# ADC2PWM.net
KiCad netlist of a schematic drawn in EAGLE
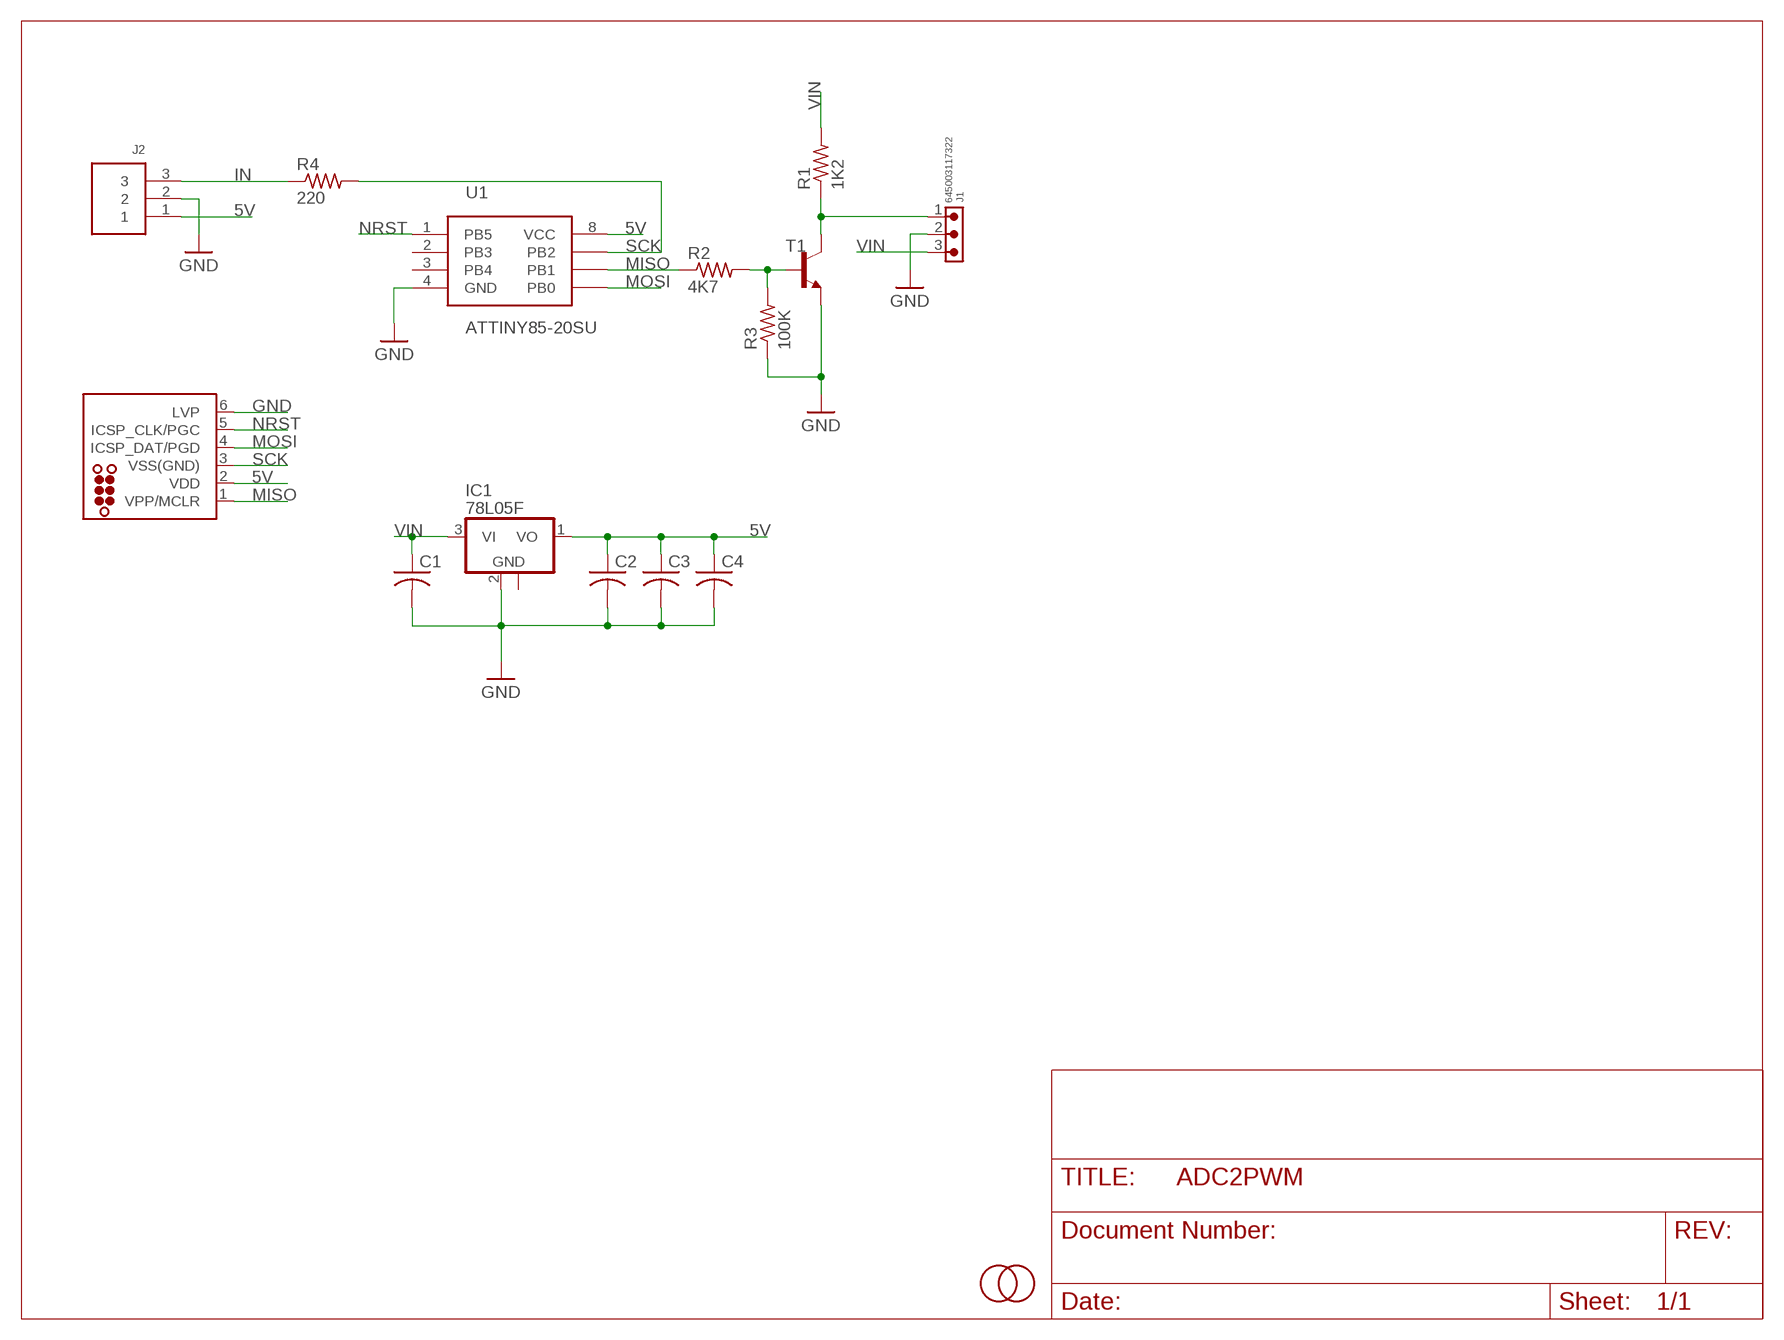
[diagram p0: schematic, sheet 1]

(export (version "E")
  (design (tool "Eeschema 10.0.6"))
  (components
    (comp (ref "C1")
      (value "C-USC0603")
      (footprint "eagle-import:C0603")
      (libsource (lib "eagle-import") (part "C-USC0603"))
    )
    (comp (ref "C2")
      (value "C-USC0603")
      (footprint "eagle-import:C0603")
      (libsource (lib "eagle-import") (part "C-USC0603"))
    )
    (comp (ref "C3")
      (value "C-USC0603")
      (footprint "eagle-import:C0603")
      (libsource (lib "eagle-import") (part "C-USC0603"))
    )
    (comp (ref "C4")
      (value "C-USC0603")
      (footprint "eagle-import:C0603")
      (libsource (lib "eagle-import") (part "C-USC0603"))
    )
    (comp (ref "IC1")
      (value "78L05F")
      (footprint "eagle-import:SOT89")
      (libsource (lib "eagle-import") (part "78LF05"))
    )
    (comp (ref "J1")
      (value "645003117322")
      (footprint "eagle-import:645003117322")
      (libsource (lib "eagle-import") (part "645003117322"))
    )
    (comp (ref "J2")
      (value "3PIN")
      (footprint "eagle-import:B3B-PH-K-S")
      (libsource (lib "eagle-import") (part "3PIN"))
    )
    (comp (ref "J3")
      (value "TC2030-MCP-NL")
      (footprint "eagle-import:TC2030-MCP-NL")
      (libsource (lib "eagle-import") (part "TC2030-MCP-NL"))
    )
    (comp (ref "R1")
      (value "1K2")
      (footprint "eagle-import:R0603")
      (libsource (lib "eagle-import") (part "R-US_R0603"))
    )
    (comp (ref "R2")
      (value "4K7")
      (footprint "eagle-import:R0603")
      (libsource (lib "eagle-import") (part "R-US_R0603"))
    )
    (comp (ref "R3")
      (value "100K")
      (footprint "eagle-import:R0603")
      (libsource (lib "eagle-import") (part "R-US_R0603"))
    )
    (comp (ref "R4")
      (value "220")
      (footprint "eagle-import:R0603")
      (libsource (lib "eagle-import") (part "R-US_R0603"))
    )
    (comp (ref "T1")
      (value "MMBT2222ALT1-NPN-SOT23-BEC")
      (footprint "eagle-import:SOT23-BEC")
      (libsource (lib "eagle-import") (part "-NPN-SOT23-BECMMBT2222ALT1"))
    )
    (comp (ref "U$1")
      (value "FIDUCIAL")
      (footprint "eagle-import:FIDUCIAL_1MM")
      (libsource (lib "eagle-import") (part "FIDUCIAL"))
    )
    (comp (ref "U$2")
      (value "FIDUCIAL")
      (footprint "eagle-import:FIDUCIAL_1MM")
      (libsource (lib "eagle-import") (part "FIDUCIAL"))
    )
    (comp (ref "U1")
      (value "ATTINY85-20SU")
      (footprint "eagle-import:SOIC-8")
      (fields
        (field (name "DIGI_KEY_PART_NUMBER") "ATTINY85-20SU-ND")
        (field (name "MANUFACTURER") "Microchip Technology")
        (field (name "CREATED_BY") "PCBLayout.com")
      )
      (libsource (lib "eagle-import") (part "ATTINY85-20SU"))
    )
  )
  (nets
    (net (code "1") (name "/5V") (class "Default")
      (node (ref "C2") (pin "1") (pinfunction "1_1") (pintype "passive"))
      (node (ref "C3") (pin "1") (pinfunction "1_1") (pintype "passive"))
      (node (ref "C4") (pin "1") (pinfunction "1_1") (pintype "passive"))
      (node (ref "IC1") (pin "1") (pinfunction "VO_1") (pintype "passive"))
      (node (ref "J2") (pin "1") (pinfunction "1_1") (pintype "bidirectional"))
      (node (ref "J3") (pin "2") (pinfunction "VDD_2") (pintype "power_in"))
      (node (ref "U1") (pin "8") (pinfunction "VCC_8") (pintype "power_in"))
    )
    (net (code "2") (name "/IN") (class "Default")
      (node (ref "J2") (pin "3") (pinfunction "3_3") (pintype "bidirectional"))
      (node (ref "R4") (pin "1") (pinfunction "1_1") (pintype "passive"))
    )
    (net (code "3") (name "/MISO") (class "Default")
      (node (ref "J3") (pin "1") (pinfunction "VPP/MCLR_1") (pintype "passive"))
      (node (ref "R2") (pin "1") (pinfunction "1_1") (pintype "passive"))
      (node (ref "U1") (pin "6") (pinfunction "PB1_6") (pintype "bidirectional"))
    )
    (net (code "4") (name "/MOSI") (class "Default")
      (node (ref "J3") (pin "4") (pinfunction "ICSP_DAT/PGD_4") (pintype "bidirectional"))
      (node (ref "U1") (pin "5") (pinfunction "PB0_5") (pintype "bidirectional"))
    )
    (net (code "5") (name "/NRST") (class "Default")
      (node (ref "J3") (pin "5") (pinfunction "ICSP_CLK/PGC_5") (pintype "output"))
      (node (ref "U1") (pin "1") (pinfunction "PB5_1") (pintype "bidirectional"))
    )
    (net (code "6") (name "/SCK") (class "Default")
      (node (ref "J3") (pin "3") (pinfunction "VSS(GND)_3") (pintype "power_in"))
      (node (ref "R4") (pin "2") (pinfunction "2_2") (pintype "passive"))
      (node (ref "U1") (pin "7") (pinfunction "PB2_7") (pintype "bidirectional"))
    )
    (net (code "7") (name "/VIN") (class "Default")
      (node (ref "C1") (pin "1") (pinfunction "1_1") (pintype "passive"))
      (node (ref "IC1") (pin "3") (pinfunction "VI_3") (pintype "input"))
      (node (ref "J1") (pin "3") (pinfunction "3_3") (pintype "passive"))
      (node (ref "R1") (pin "2") (pinfunction "2_2") (pintype "passive"))
    )
    (net (code "8") (name "GND") (class "Default")
      (node (ref "C1") (pin "2") (pinfunction "2_2") (pintype "passive"))
      (node (ref "C2") (pin "2") (pinfunction "2_2") (pintype "passive"))
      (node (ref "C3") (pin "2") (pinfunction "2_2") (pintype "passive"))
      (node (ref "C4") (pin "2") (pinfunction "2_2") (pintype "passive"))
      (node (ref "IC1") (pin "2") (pinfunction "GND_2") (pintype "passive"))
      (node (ref "J1") (pin "2") (pinfunction "2_2") (pintype "passive"))
      (node (ref "J2") (pin "2") (pinfunction "2_2") (pintype "bidirectional"))
      (node (ref "J3") (pin "6") (pinfunction "LVP_6") (pintype "bidirectional"))
      (node (ref "R3") (pin "1") (pinfunction "1_1") (pintype "passive"))
      (node (ref "T1") (pin "E") (pinfunction "E_E") (pintype "passive"))
      (node (ref "U1") (pin "4") (pinfunction "GND_4") (pintype "power_in"))
    )
    (net (code "9") (name "Net-(J1-Pad1)") (class "Default")
      (node (ref "J1") (pin "1") (pinfunction "1_1") (pintype "passive"))
      (node (ref "R1") (pin "1") (pinfunction "1_1") (pintype "passive"))
      (node (ref "T1") (pin "C") (pinfunction "C_C") (pintype "passive"))
    )
    (net (code "10") (name "Net-(R2-Pad2)") (class "Default")
      (node (ref "R2") (pin "2") (pinfunction "2_2") (pintype "passive"))
      (node (ref "R3") (pin "2") (pinfunction "2_2") (pintype "passive"))
      (node (ref "T1") (pin "B") (pinfunction "B_B") (pintype "passive"))
    )
    (net (code "11") (name "unconnected-(IC1-GND-Pad2@1)") (class "Default")
      (node (ref "IC1") (pin "2@1") (pinfunction "GND_2@1") (pintype "passive"))
    )
    (net (code "12") (name "unconnected-(U1-PB3-Pad2)") (class "Default")
      (node (ref "U1") (pin "2") (pinfunction "PB3_2") (pintype "bidirectional"))
    )
    (net (code "13") (name "unconnected-(U1-PB4-Pad3)") (class "Default")
      (node (ref "U1") (pin "3") (pinfunction "PB4_3") (pintype "bidirectional"))
    )
  )
)
